# schematic.net
KiCad netlist of a schematic drawn in EasyEDA
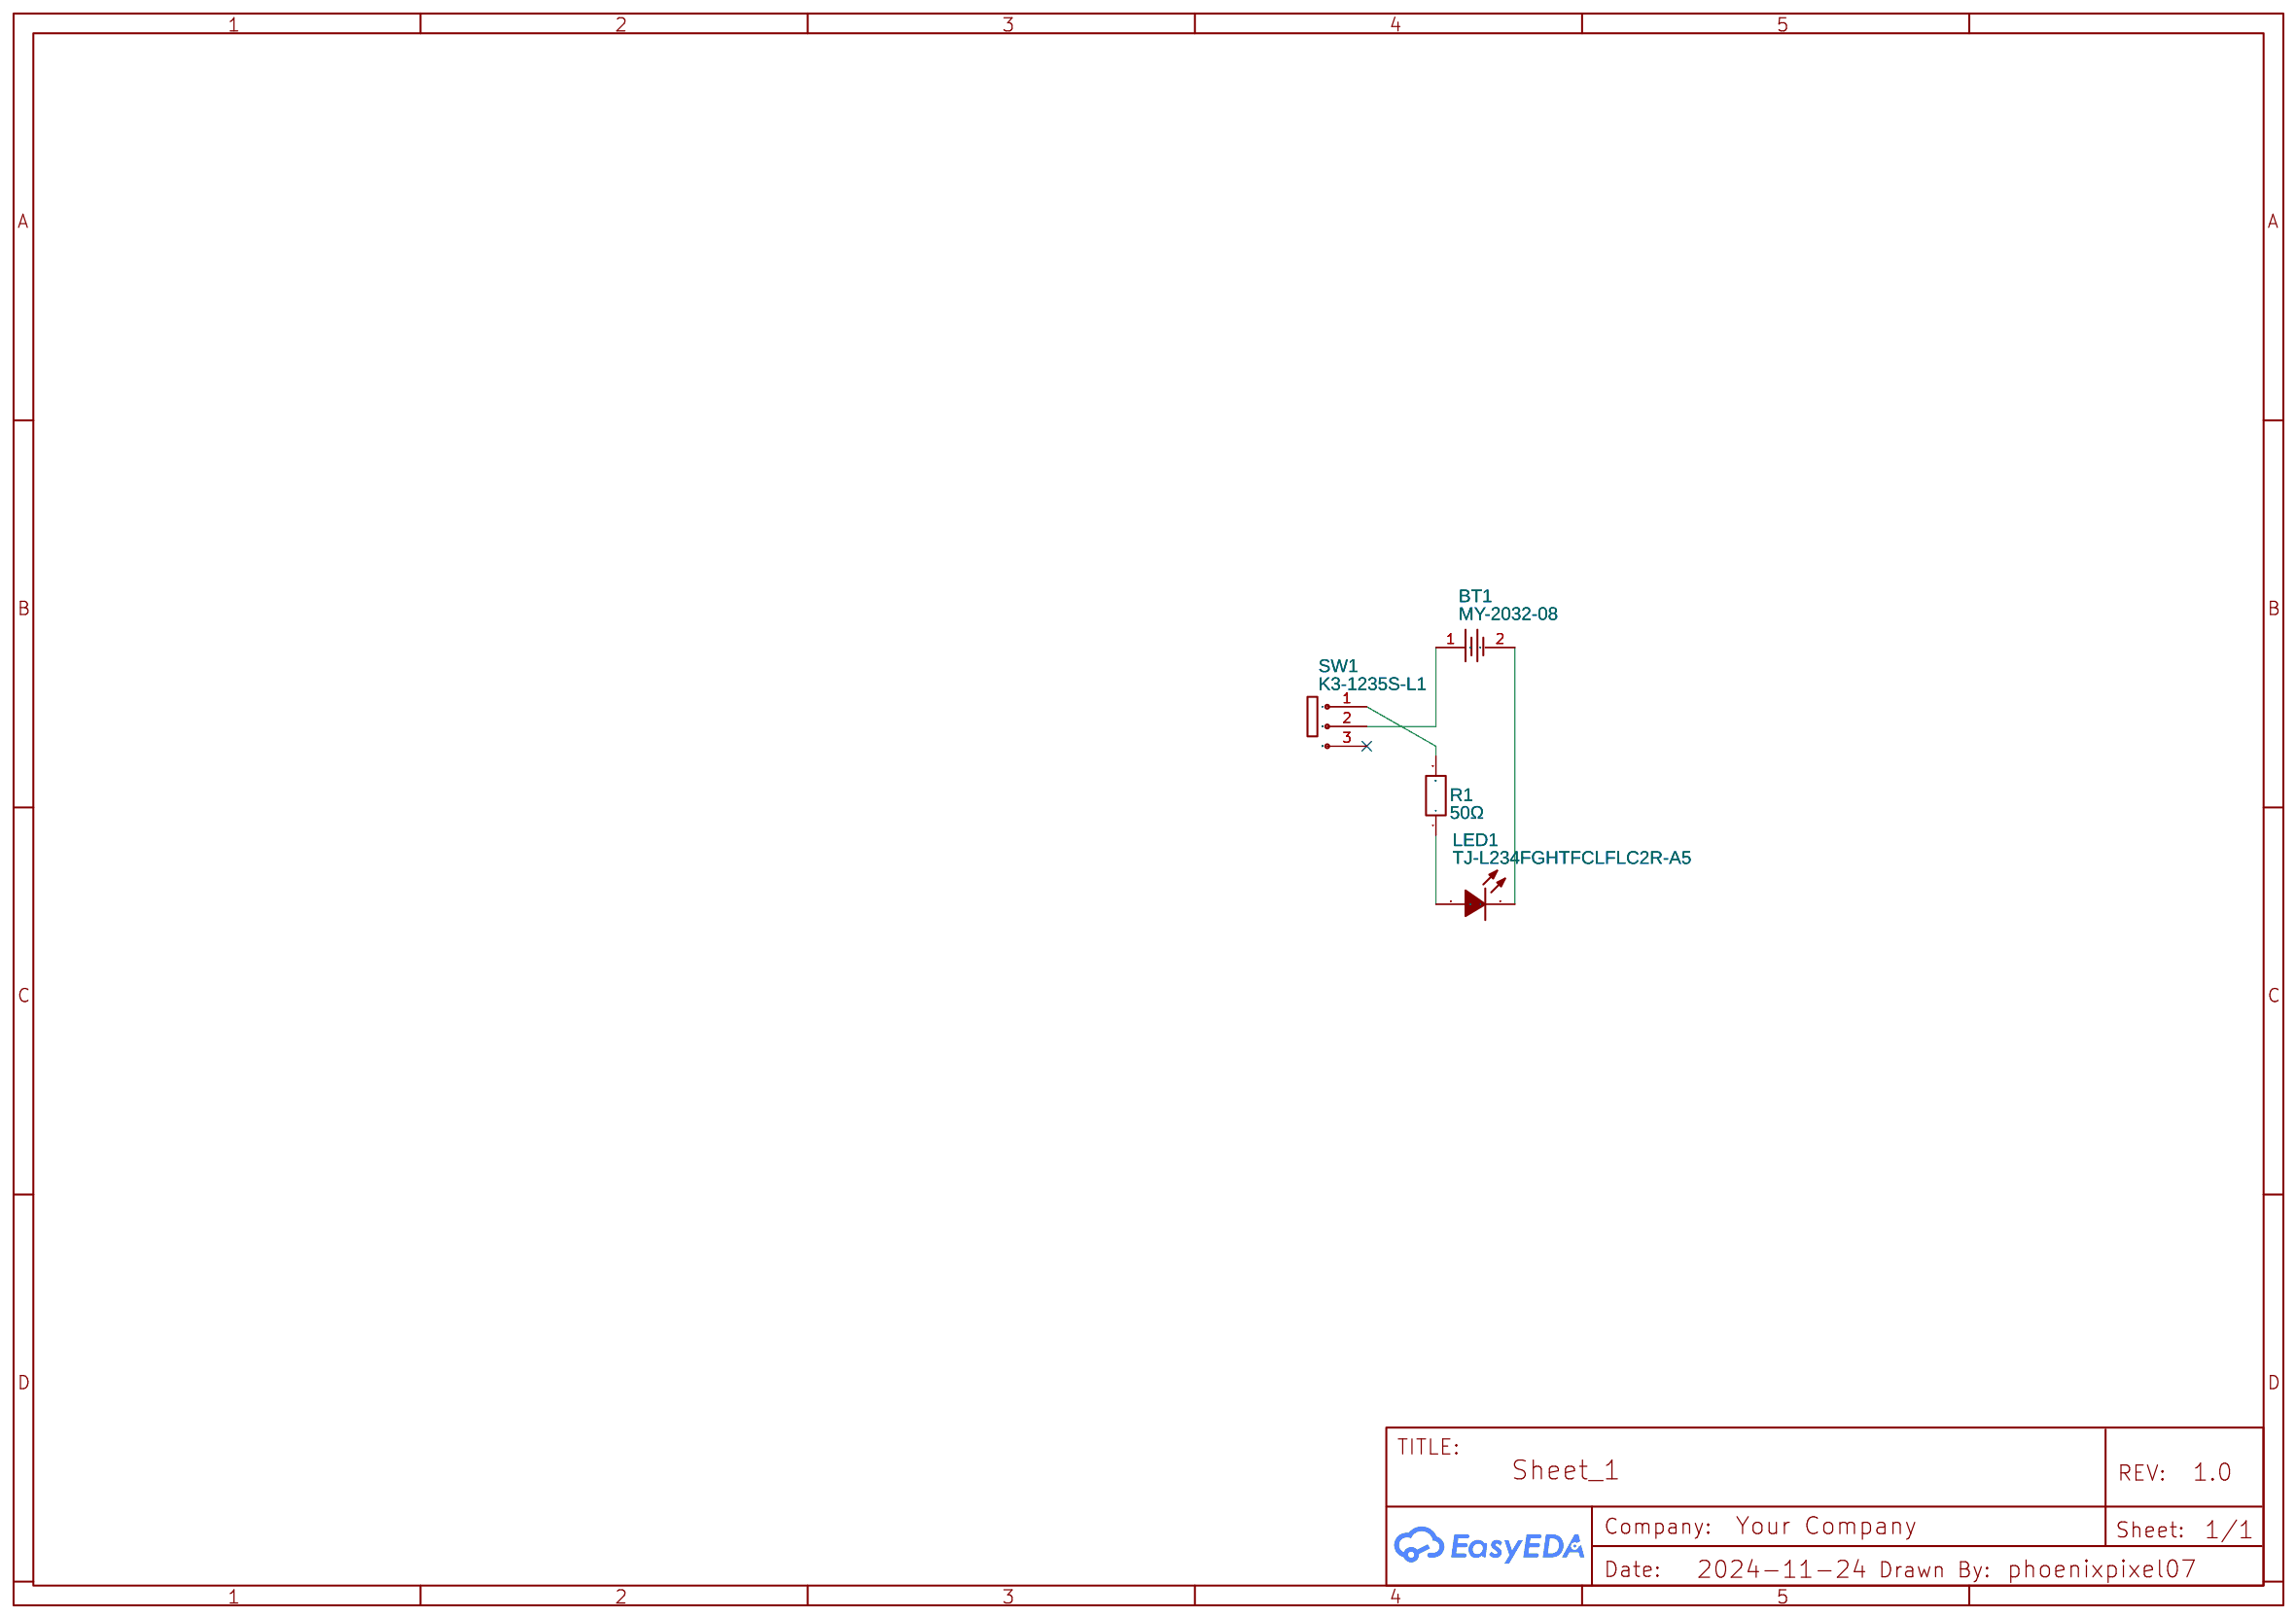
[diagram p0: schematic sheet]

(export (version "E")
  (design (tool "Eeschema 10.0.6"))
  (components
    (comp (ref "BT1")
      (value "MY-2032-08")
      (fields (field (name "Manufacturer") "MYOUNG(美阳)"))
      (libsource (lib "") (part "MY-2032-08"))
    )
    (comp (ref "LED1")
      (value "TJ-L234FGHTFCLFLC2R-A5")
      (fields (field (name "Manufacturer") "TOGIALED(统佳)"))
      (libsource (lib "") (part "TJ-L234FGHTFCLFLC2R-A5"))
    )
    (comp (ref "R1")
      (value "50Ω")
      (fields (field (name "Manufacturer Part") "AR10FTCO0500") (field (name "Manufacturer") "Viking(光颉)"))
      (libsource (lib "") (part "AR10FTCO0500"))
    )
    (comp (ref "SW1")
      (value "K3-1235S-L1")
      (fields (field (name "Manufacturer") "韩国韩荣"))
      (libsource (lib "") (part "K3-1235S-L1"))
    )
  )
  (nets
    (net (code "1") (name "Net-(BT1-Pad1)") (class "Default")
      (node (ref "BT1") (pin "1") (pinfunction "1_1") (pintype "input"))
      (node (ref "SW1") (pin "2") (pinfunction "2_2") (pintype "unspecified"))
    )
    (net (code "2") (name "Net-(LED1-A)") (class "Default")
      (node (ref "LED1") (pin "1") (pinfunction "A_1") (pintype "unspecified"))
      (node (ref "R1") (pin "1") (pinfunction "1_1") (pintype "unspecified"))
    )
    (net (code "3") (name "Net-(LED1-K)") (class "Default")
      (node (ref "BT1") (pin "2") (pinfunction "2_2") (pintype "input"))
      (node (ref "LED1") (pin "2") (pinfunction "K_2") (pintype "unspecified"))
    )
    (net (code "4") (name "Net-(R1-Pad2)") (class "Default")
      (node (ref "R1") (pin "2") (pinfunction "2_2") (pintype "unspecified"))
      (node (ref "SW1") (pin "1") (pinfunction "1_1") (pintype "unspecified"))
    )
    (net (code "5") (name "unconnected-(SW1-Pad3)") (class "Default")
      (node (ref "SW1") (pin "3") (pinfunction "3_3") (pintype "unspecified+no_connect"))
    )
  )
)
